# etapa3.net
KiCad netlist of a schematic drawn in Altium Designer
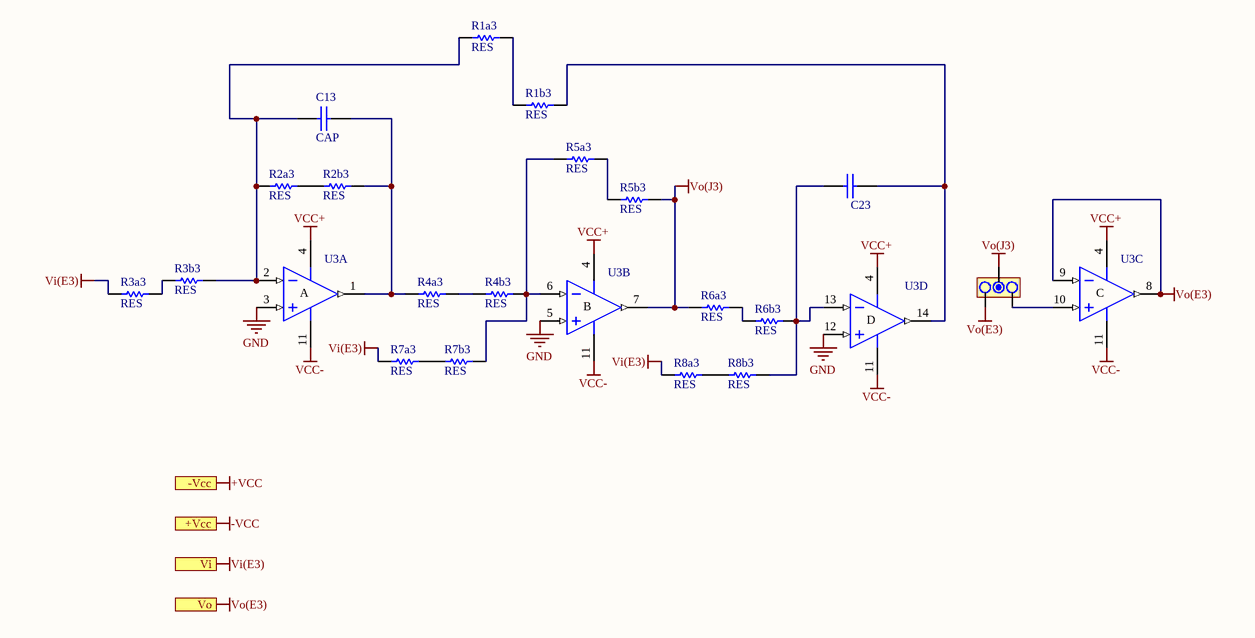
[diagram p0: etapa3.SchDoc]

(export (version "E")
  (design (tool "Eeschema 10.0.6"))
  (components
    (comp (ref "C13") (value "CAP") (footprint "CAP200") (libsource (lib "LIBEBAL") (part "CAP")))
    (comp (ref "C23") (value "CAP") (footprint "CAP200") (libsource (lib "LIBEBAL") (part "CAP")))
    (comp (ref "Jumper3") (value "JUMPER") (footprint "JUMPER3") (libsource (lib "LIBEBAL") (part "JUMPER3")))
    (comp (ref "R1a3") (value "RES") (footprint "0805") (libsource (lib "LIBEBAL") (part "RES")))
    (comp (ref "R1b3") (value "RES") (footprint "0805") (libsource (lib "LIBEBAL") (part "RES")))
    (comp (ref "R2a3") (value "RES") (footprint "0805") (libsource (lib "LIBEBAL") (part "RES")))
    (comp (ref "R2b3") (value "RES") (footprint "0805") (libsource (lib "LIBEBAL") (part "RES")))
    (comp (ref "R3a3") (value "RES") (footprint "0805") (libsource (lib "LIBEBAL") (part "RES")))
    (comp (ref "R3b3") (value "RES") (footprint "0805") (libsource (lib "LIBEBAL") (part "RES")))
    (comp (ref "R4a3") (value "RES") (footprint "0805") (libsource (lib "LIBEBAL") (part "RES")))
    (comp (ref "R4b3") (value "RES") (footprint "0805") (libsource (lib "LIBEBAL") (part "RES")))
    (comp (ref "R5a3") (value "RES") (footprint "0805") (libsource (lib "LIBEBAL") (part "RES")))
    (comp (ref "R5b3") (value "RES") (footprint "0805") (libsource (lib "LIBEBAL") (part "RES")))
    (comp (ref "R6a3") (value "RES") (footprint "0805") (libsource (lib "LIBEBAL") (part "RES")))
    (comp (ref "R6b3") (value "RES") (footprint "0805") (libsource (lib "LIBEBAL") (part "RES")))
    (comp (ref "R7a3") (value "RES") (footprint "0805") (libsource (lib "LIBEBAL") (part "RES")))
    (comp (ref "R7b3") (value "RES") (footprint "0805") (libsource (lib "LIBEBAL") (part "RES")))
    (comp (ref "R8a3") (value "RES") (footprint "0805") (libsource (lib "LIBEBAL") (part "RES")))
    (comp (ref "R8b3") (value "RES") (footprint "0805") (libsource (lib "LIBEBAL") (part "RES")))
    (comp (ref "U3")
      (value "TL084N")
      (footprint "N014")
      (description "JFET-Input Operational Amplifier")
      (fields (field (name "PUBLISHER") "Altium Limited"))
      (libsource (lib "TI Operational Amplifier") (part "TL084N"))
    )
  )
  (nets
    (net (code "3") (name "GND") (class "Default")
      (node (ref "U3") (pin "12") (pinfunction "IN+_12") (pintype "input"))
      (node (ref "U3") (pin "3") (pinfunction "IN+_3") (pintype "input"))
      (node (ref "U3") (pin "5") (pinfunction "IN+_5") (pintype "input"))
    )
    (net (code "4") (name "Net-(R1a3-Pad2)") (class "Default")
      (node (ref "R1a3") (pin "2") (pinfunction "2_2") (pintype "passive"))
      (node (ref "R1b3") (pin "1") (pinfunction "1_1") (pintype "passive"))
    )
    (net (code "5") (name "Net-(R2a3-Pad2)") (class "Default")
      (node (ref "R2a3") (pin "2") (pinfunction "2_2") (pintype "passive"))
      (node (ref "R2b3") (pin "1") (pinfunction "1_1") (pintype "passive"))
    )
    (net (code "6") (name "Net-(R3a3-Pad2)") (class "Default")
      (node (ref "R3a3") (pin "2") (pinfunction "2_2") (pintype "passive"))
      (node (ref "R3b3") (pin "1") (pinfunction "1_1") (pintype "passive"))
    )
    (net (code "7") (name "Net-(R4a3-Pad2)") (class "Default")
      (node (ref "R4a3") (pin "2") (pinfunction "2_2") (pintype "passive"))
      (node (ref "R4b3") (pin "1") (pinfunction "1_1") (pintype "passive"))
    )
    (net (code "8") (name "Net-(R5a3-Pad2)") (class "Default")
      (node (ref "R5a3") (pin "2") (pinfunction "2_2") (pintype "passive"))
      (node (ref "R5b3") (pin "1") (pinfunction "1_1") (pintype "passive"))
    )
    (net (code "9") (name "Net-(R6a3-Pad2)") (class "Default")
      (node (ref "R6a3") (pin "2") (pinfunction "2_2") (pintype "passive"))
      (node (ref "R6b3") (pin "1") (pinfunction "1_1") (pintype "passive"))
    )
    (net (code "10") (name "Net-(R7a3-Pad2)") (class "Default")
      (node (ref "R7a3") (pin "2") (pinfunction "2_2") (pintype "passive"))
      (node (ref "R7b3") (pin "1") (pinfunction "1_1") (pintype "passive"))
    )
    (net (code "11") (name "Net-(R8a3-Pad2)") (class "Default")
      (node (ref "R8a3") (pin "2") (pinfunction "2_2") (pintype "passive"))
      (node (ref "R8b3") (pin "1") (pinfunction "1_1") (pintype "passive"))
    )
    (net (code "12") (name "Net-(U3A-IN-)") (class "Default")
      (node (ref "C13") (pin "1") (pinfunction "1_1") (pintype "passive"))
      (node (ref "R1a3") (pin "1") (pinfunction "1_1") (pintype "passive"))
      (node (ref "R2a3") (pin "1") (pinfunction "1_1") (pintype "passive"))
      (node (ref "R3b3") (pin "2") (pinfunction "2_2") (pintype "passive"))
      (node (ref "U3") (pin "2") (pinfunction "IN-_2") (pintype "input"))
    )
    (net (code "13") (name "Net-(U3A-OUT)") (class "Default")
      (node (ref "C13") (pin "2") (pinfunction "2_2") (pintype "passive"))
      (node (ref "R2b3") (pin "2") (pinfunction "2_2") (pintype "passive"))
      (node (ref "R4a3") (pin "1") (pinfunction "1_1") (pintype "passive"))
      (node (ref "U3") (pin "1") (pinfunction "OUT_1") (pintype "output"))
    )
    (net (code "14") (name "Net-(U3B-IN-)") (class "Default")
      (node (ref "R4b3") (pin "2") (pinfunction "2_2") (pintype "passive"))
      (node (ref "R5a3") (pin "1") (pinfunction "1_1") (pintype "passive"))
      (node (ref "R7b3") (pin "2") (pinfunction "2_2") (pintype "passive"))
      (node (ref "U3") (pin "6") (pinfunction "IN-_6") (pintype "input"))
    )
    (net (code "15") (name "Net-(U3C-IN+)") (class "Default")
      (node (ref "Jumper3") (pin "1") (pinfunction "1_1") (pintype "passive"))
      (node (ref "U3") (pin "10") (pinfunction "IN+_10") (pintype "input"))
    )
    (net (code "16") (name "Net-(U3D-IN-)") (class "Default")
      (node (ref "C23") (pin "1") (pinfunction "1_1") (pintype "passive"))
      (node (ref "R6b3") (pin "2") (pinfunction "2_2") (pintype "passive"))
      (node (ref "R8b3") (pin "2") (pinfunction "2_2") (pintype "passive"))
      (node (ref "U3") (pin "13") (pinfunction "IN-_13") (pintype "input"))
    )
    (net (code "17") (name "Net-(U3D-OUT)") (class "Default")
      (node (ref "C23") (pin "2") (pinfunction "2_2") (pintype "passive"))
      (node (ref "R1b3") (pin "2") (pinfunction "2_2") (pintype "passive"))
      (node (ref "U3") (pin "14") (pinfunction "OUT_14") (pintype "output"))
    )
    (net (code "18") (name "VCC+") (class "Default")
      (node (ref "U3") (pin "4") (pinfunction "V+_4") (pintype "power_in"))
    )
    (net (code "19") (name "VCC-") (class "Default")
      (node (ref "U3") (pin "11") (pinfunction "V-_11") (pintype "power_in"))
    )
    (net (code "20") (name "Vi(E3)") (class "Default")
      (node (ref "R3a3") (pin "1") (pinfunction "1_1") (pintype "passive"))
      (node (ref "R7a3") (pin "1") (pinfunction "1_1") (pintype "passive"))
      (node (ref "R8a3") (pin "1") (pinfunction "1_1") (pintype "passive"))
    )
    (net (code "21") (name "Vo(E3)") (class "Default")
      (node (ref "Jumper3") (pin "3") (pinfunction "3_3") (pintype "passive"))
      (node (ref "U3") (pin "8") (pinfunction "OUT_8") (pintype "output"))
      (node (ref "U3") (pin "9") (pinfunction "IN-_9") (pintype "input"))
    )
    (net (code "22") (name "Vo(J3)") (class "Default")
      (node (ref "Jumper3") (pin "2") (pinfunction "2_2") (pintype "passive"))
      (node (ref "R5b3") (pin "2") (pinfunction "2_2") (pintype "passive"))
      (node (ref "R6a3") (pin "1") (pinfunction "1_1") (pintype "passive"))
      (node (ref "U3") (pin "7") (pinfunction "OUT_7") (pintype "output"))
    )
  )
)
